# IMU.net
KiCad netlist of a schematic drawn in Altium Designer
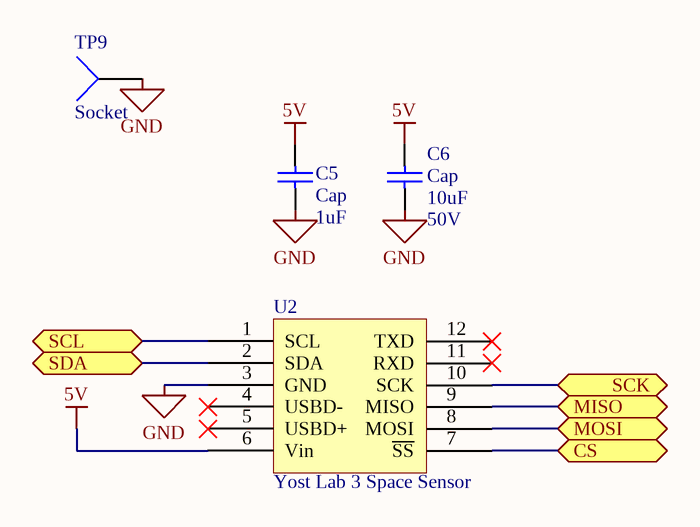
[diagram p0: IMU.SchDoc]

(export (version "E")
  (design (tool "Eeschema 10.0.6"))
  (components
    (comp (ref "C5")
      (value "Cap")
      (footprint "RESC3116X65N")
      (description "Capacitor")
      (fields
        (field (name "ALTIUM_VALUE") "1uF")
        (field (name "MANUFACTURER PART NUMBER") "CL31B105KCHNNNE")
        (field (name "VENDOR PART NUMBER") "1276-1838-1-ND")
      )
      (libsource (lib "Miscellaneous Devices") (part "Cap"))
    )
    (comp (ref "C6")
      (value "Cap")
      (footprint "CAPC3216X180N")
      (description "Capacitor")
      (fields
        (field (name "ALTIUM_VALUE") "10uF")
        (field (name "MANUFACTURER PART NUMBER") "CL31A106MBHNNNE")
        (field (name "VENDOR PART NUMBER") "1276-6736-1-ND")
        (field (name "VOLTAGE RATING") "50V")
      )
      (libsource (lib "Miscellaneous Devices") (part "Cap"))
    )
    (comp (ref "TP9")
      (value "Socket")
      (footprint "5006")
      (fields
        (field (name "MANUFACTURER PART NUMBER") "5006")
        (field (name "VENDOR PART NUMBER") "36-5006-ND")
        (field (name "PUBLISHER") "Altium Limited")
      )
      (libsource (lib "Miscellaneous Connectors") (part "Socket"))
    )
    (comp (ref "U2")
      (value "Yost Lab 3 Space Sensor")
      (footprint "Yost 3 Space Sensor")
      (libsource (lib "BeagleCape") (part "Yost Lab 3 Space Sensor"))
    )
  )
  (nets
    (net (code "1") (name "/CS") (class "Default")
      (node (ref "U2") (pin "7") (pinfunction "~{SS}_7") (pintype "passive"))
    )
    (net (code "2") (name "/MISO") (class "Default")
      (node (ref "U2") (pin "9") (pinfunction "MISO_9") (pintype "passive"))
    )
    (net (code "3") (name "/MOSI") (class "Default")
      (node (ref "U2") (pin "8") (pinfunction "MOSI_8") (pintype "passive"))
    )
    (net (code "4") (name "/SCK") (class "Default")
      (node (ref "U2") (pin "10") (pinfunction "SCK_10") (pintype "passive"))
    )
    (net (code "5") (name "/SCL") (class "Default")
      (node (ref "U2") (pin "1") (pinfunction "SCL_1") (pintype "passive"))
    )
    (net (code "6") (name "/SDA") (class "Default")
      (node (ref "U2") (pin "2") (pinfunction "SDA_2") (pintype "passive"))
    )
    (net (code "7") (name "5V") (class "Default")
      (node (ref "C5") (pin "2") (pinfunction "2_2") (pintype "passive"))
      (node (ref "C6") (pin "2") (pinfunction "2_2") (pintype "passive"))
      (node (ref "U2") (pin "6") (pinfunction "Vin_6") (pintype "passive"))
    )
    (net (code "8") (name "GND") (class "Default")
      (node (ref "C5") (pin "1") (pinfunction "1_1") (pintype "passive"))
      (node (ref "C6") (pin "1") (pinfunction "1_1") (pintype "passive"))
      (node (ref "TP9") (pin "1") (pinfunction "1_1") (pintype "passive"))
      (node (ref "U2") (pin "3") (pinfunction "GND_3") (pintype "passive"))
    )
    (net (code "9") (name "unconnected-(U2-RXD-Pad11)") (class "Default")
      (node (ref "U2") (pin "11") (pinfunction "RXD_11") (pintype "passive+no_connect"))
    )
    (net (code "10") (name "unconnected-(U2-TXD-Pad12)") (class "Default")
      (node (ref "U2") (pin "12") (pinfunction "TXD_12") (pintype "passive+no_connect"))
    )
    (net (code "11") (name "unconnected-(U2-USBD+-Pad5)") (class "Default")
      (node (ref "U2") (pin "5") (pinfunction "USBD+_5") (pintype "passive+no_connect"))
    )
    (net (code "12") (name "unconnected-(U2-USBD--Pad4)") (class "Default")
      (node (ref "U2") (pin "4") (pinfunction "USBD-_4") (pintype "passive+no_connect"))
    )
  )
)
